# FPGA_Power.net
KiCad netlist of a schematic drawn in Altium Designer
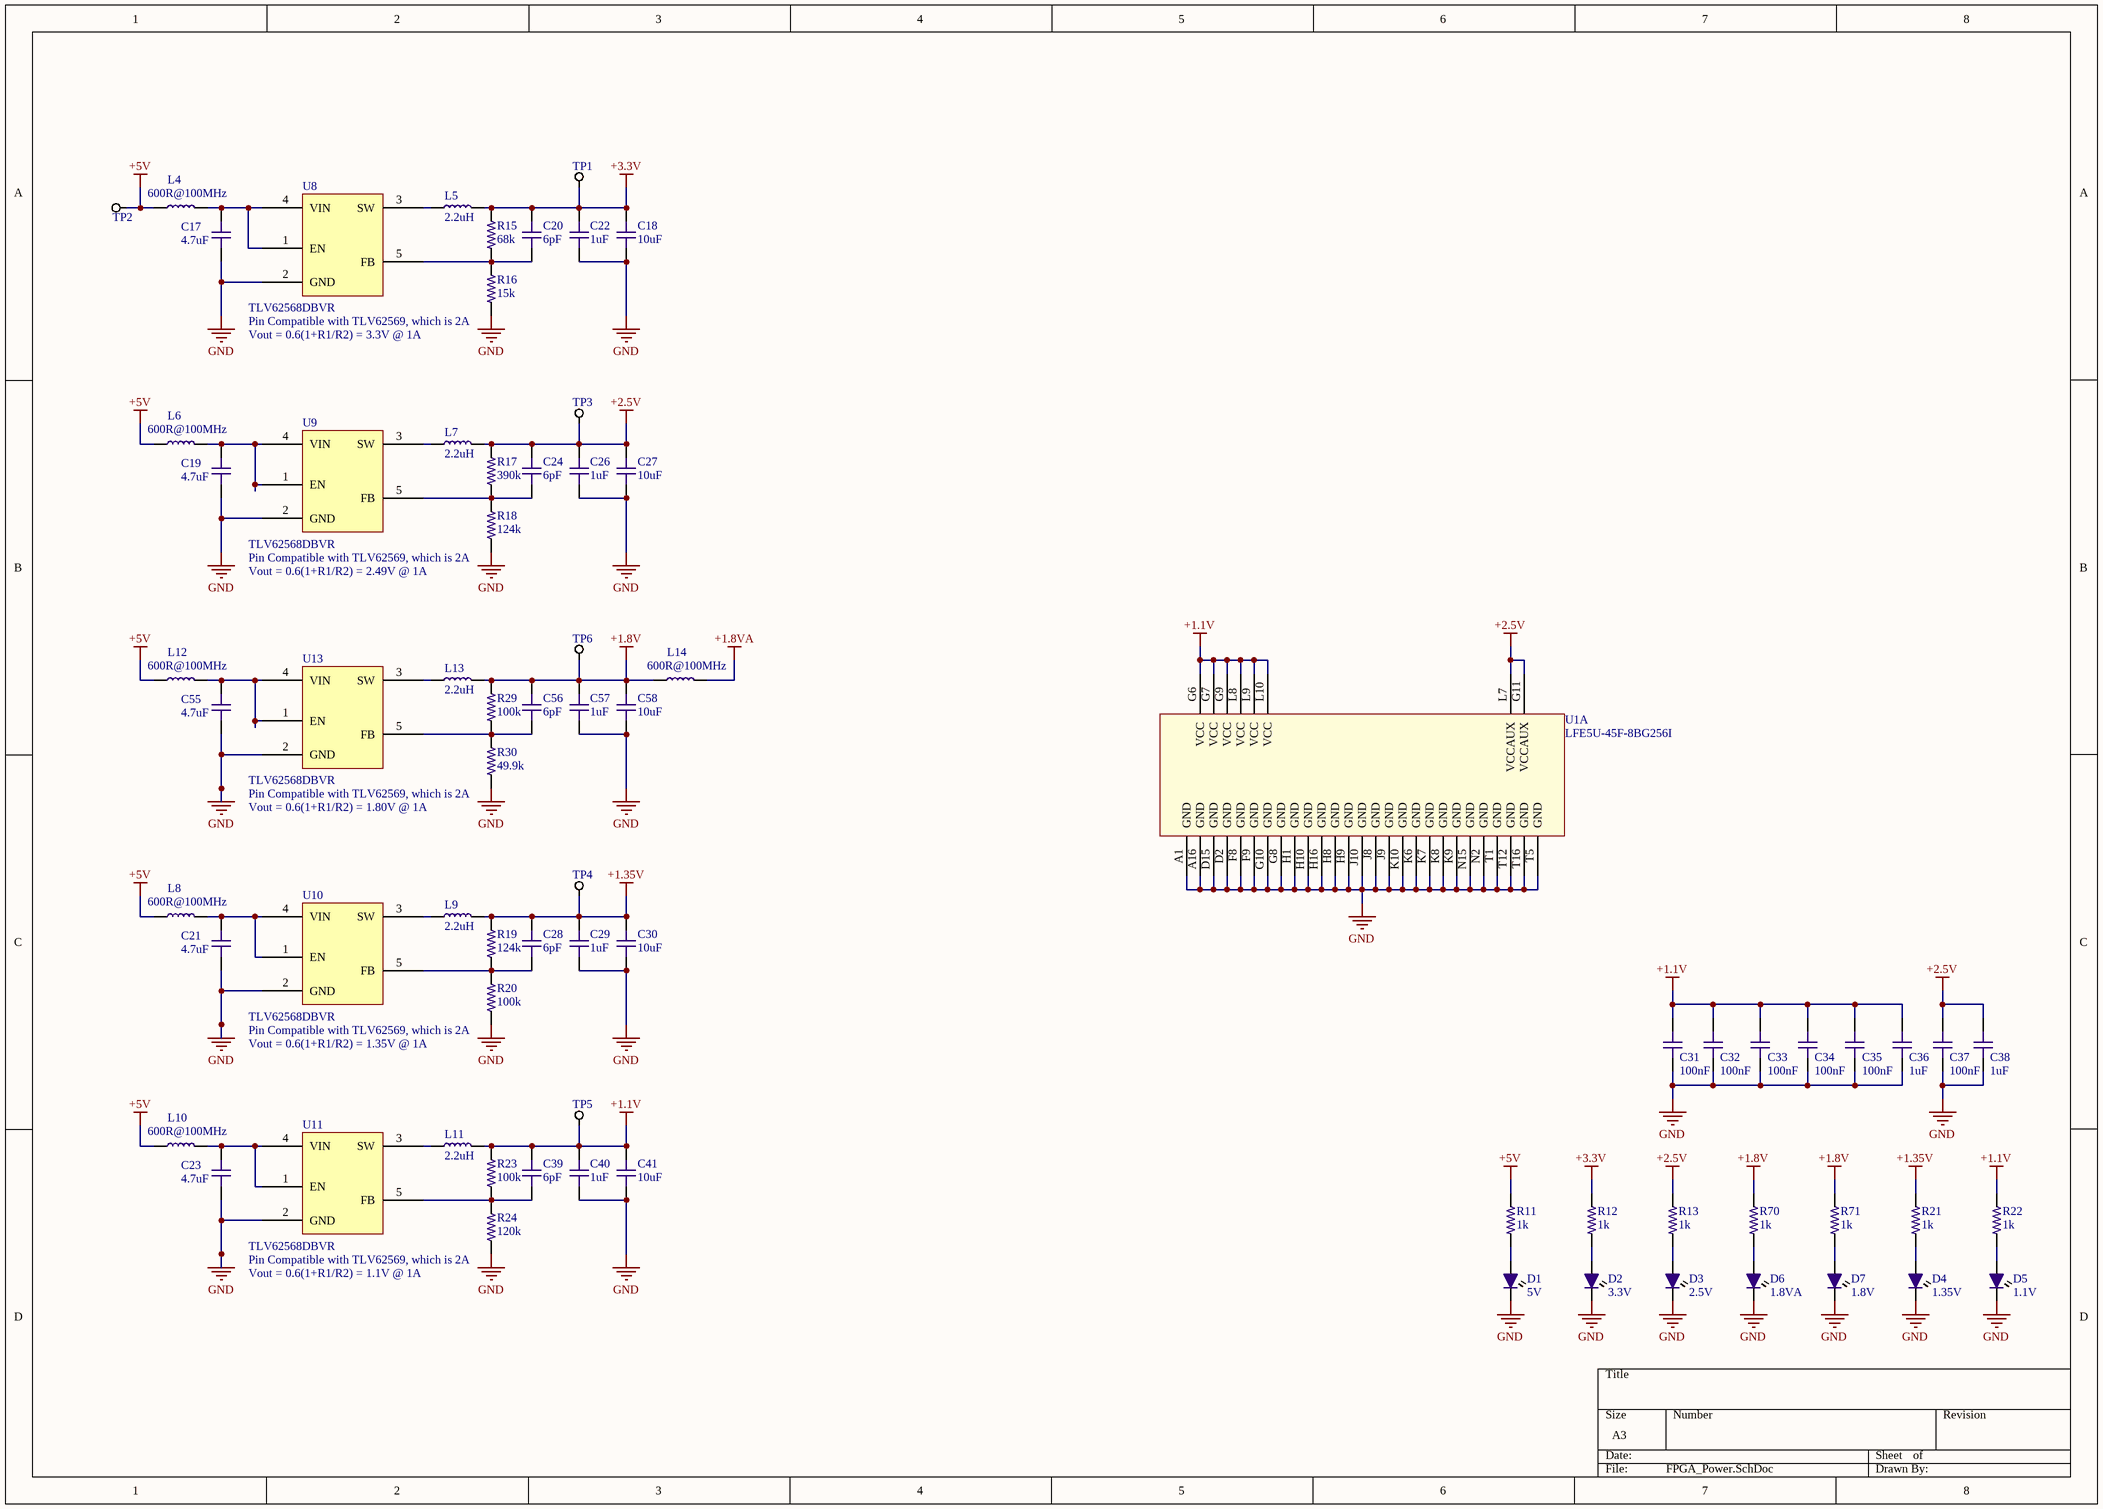
[diagram p0: FPGA_Power.SchDoc]

(export (version "E")
  (design (tool "Eeschema 10.0.6"))
  (components
    (comp (ref "C17")
      (value "4.7uF")
      (footprint "C0603-HIGH-DENSITY")
      (description "Chip Capacitor, 0603, 4.7uF, 25V, X5R")
      (fields (field (name "Comment") "4.7uF, 25V, X5R, 0603"))
      (libsource (lib "Capacitors") (part "C0603 4.7uF 25V X5R"))
    )
    (comp (ref "C18")
      (value "10uF")
      (footprint "C0603-HIGH-DENSITY")
      (description "Chip Capacitor, 0603, 10uF, 10V, X5R")
      (fields (field (name "Comment") "C0603 10uF 10V X5R"))
      (libsource (lib "Capacitors") (part "C0603 10uF 10V X5R"))
    )
    (comp (ref "C19")
      (value "4.7uF")
      (footprint "C0603-HIGH-DENSITY")
      (description "Chip Capacitor, 0603, 4.7uF, 25V, X5R")
      (fields (field (name "Comment") "4.7uF, 25V, X5R, 0603"))
      (libsource (lib "Capacitors") (part "C0603 4.7uF 25V X5R"))
    )
    (comp (ref "C20")
      (value "6pF")
      (footprint "C0603-HIGH-DENSITY")
      (description "CAP CER 6PF 50V C0G/NP0 0603")
      (fields (field (name "Comment") "CL10C060DB8NNNC"))
      (libsource (lib "Capacitors") (part "C0603 6pF 50V C0G"))
    )
    (comp (ref "C21")
      (value "4.7uF")
      (footprint "C0603-HIGH-DENSITY")
      (description "Chip Capacitor, 0603, 4.7uF, 25V, X5R")
      (fields (field (name "Comment") "4.7uF, 25V, X5R, 0603"))
      (libsource (lib "Capacitors") (part "C0603 4.7uF 25V X5R"))
    )
    (comp (ref "C22")
      (value "1uF")
      (footprint "C0603-HIGH-DENSITY")
      (description "CAP CER 1UF 25V X7R 0603")
      (fields (field (name "Comment") "C0603 1uF 25V X7R"))
      (libsource (lib "Capacitors") (part "C0603 1uF 25V X7R"))
    )
    (comp (ref "C23")
      (value "4.7uF")
      (footprint "C0603-HIGH-DENSITY")
      (description "Chip Capacitor, 0603, 4.7uF, 25V, X5R")
      (fields (field (name "Comment") "4.7uF, 25V, X5R, 0603"))
      (libsource (lib "Capacitors") (part "C0603 4.7uF 25V X5R"))
    )
    (comp (ref "C24")
      (value "6pF")
      (footprint "C0603-HIGH-DENSITY")
      (description "CAP CER 6PF 50V C0G/NP0 0603")
      (fields (field (name "Comment") "CL10C060DB8NNNC"))
      (libsource (lib "Capacitors") (part "C0603 6pF 50V C0G"))
    )
    (comp (ref "C26")
      (value "1uF")
      (footprint "C0603-HIGH-DENSITY")
      (description "CAP CER 1UF 25V X7R 0603")
      (fields (field (name "Comment") "C0603 1uF 25V X7R"))
      (libsource (lib "Capacitors") (part "C0603 1uF 25V X7R"))
    )
    (comp (ref "C27")
      (value "10uF")
      (footprint "C0603-HIGH-DENSITY")
      (description "Chip Capacitor, 0603, 10uF, 10V, X5R")
      (fields (field (name "Comment") "C0603 10uF 10V X5R"))
      (libsource (lib "Capacitors") (part "C0603 10uF 10V X5R"))
    )
    (comp (ref "C28")
      (value "6pF")
      (footprint "C0603-HIGH-DENSITY")
      (description "CAP CER 6PF 50V C0G/NP0 0603")
      (fields (field (name "Comment") "CL10C060DB8NNNC"))
      (libsource (lib "Capacitors") (part "C0603 6pF 50V C0G"))
    )
    (comp (ref "C29")
      (value "1uF")
      (footprint "C0603-HIGH-DENSITY")
      (description "CAP CER 1UF 25V X7R 0603")
      (fields (field (name "Comment") "C0603 1uF 25V X7R"))
      (libsource (lib "Capacitors") (part "C0603 1uF 25V X7R"))
    )
    (comp (ref "C30")
      (value "10uF")
      (footprint "C0603-HIGH-DENSITY")
      (description "Chip Capacitor, 0603, 10uF, 10V, X5R")
      (fields (field (name "Comment") "C0603 10uF 10V X5R"))
      (libsource (lib "Capacitors") (part "C0603 10uF 10V X5R"))
    )
    (comp (ref "C31")
      (value "100nF")
      (footprint "C0603-HIGH-DENSITY")
      (description "Chip Capacitor, 0603, 100nF, 25V, X7R")
      (fields (field (name "Comment") "C0603 100nF 25V X7R"))
      (libsource (lib "Capacitors") (part "C0603 100nF 25V X7R"))
    )
    (comp (ref "C32")
      (value "100nF")
      (footprint "C0603-HIGH-DENSITY")
      (description "Chip Capacitor, 0603, 100nF, 25V, X7R")
      (fields (field (name "Comment") "C0603 100nF 25V X7R"))
      (libsource (lib "Capacitors") (part "C0603 100nF 25V X7R"))
    )
    (comp (ref "C33")
      (value "100nF")
      (footprint "C0603-HIGH-DENSITY")
      (description "Chip Capacitor, 0603, 100nF, 25V, X7R")
      (fields (field (name "Comment") "C0603 100nF 25V X7R"))
      (libsource (lib "Capacitors") (part "C0603 100nF 25V X7R"))
    )
    (comp (ref "C34")
      (value "100nF")
      (footprint "C0603-HIGH-DENSITY")
      (description "Chip Capacitor, 0603, 100nF, 25V, X7R")
      (fields (field (name "Comment") "C0603 100nF 25V X7R"))
      (libsource (lib "Capacitors") (part "C0603 100nF 25V X7R"))
    )
    (comp (ref "C35")
      (value "100nF")
      (footprint "C0603-HIGH-DENSITY")
      (description "Chip Capacitor, 0603, 100nF, 25V, X7R")
      (fields (field (name "Comment") "C0603 100nF 25V X7R"))
      (libsource (lib "Capacitors") (part "C0603 100nF 25V X7R"))
    )
    (comp (ref "C36")
      (value "1uF")
      (footprint "C0603-HIGH-DENSITY")
      (description "CAP CER 1UF 25V X7R 0603")
      (fields (field (name "Comment") "C0603 1uF 25V X7R"))
      (libsource (lib "Capacitors") (part "C0603 1uF 25V X7R"))
    )
    (comp (ref "C37")
      (value "100nF")
      (footprint "C0603-HIGH-DENSITY")
      (description "Chip Capacitor, 0603, 100nF, 25V, X7R")
      (fields (field (name "Comment") "C0603 100nF 25V X7R"))
      (libsource (lib "Capacitors") (part "C0603 100nF 25V X7R"))
    )
    (comp (ref "C38")
      (value "1uF")
      (footprint "C0603-HIGH-DENSITY")
      (description "CAP CER 1UF 25V X7R 0603")
      (fields (field (name "Comment") "C0603 1uF 25V X7R"))
      (libsource (lib "Capacitors") (part "C0603 1uF 25V X7R"))
    )
    (comp (ref "C39")
      (value "6pF")
      (footprint "C0603-HIGH-DENSITY")
      (description "CAP CER 6PF 50V C0G/NP0 0603")
      (fields (field (name "Comment") "CL10C060DB8NNNC"))
      (libsource (lib "Capacitors") (part "C0603 6pF 50V C0G"))
    )
    (comp (ref "C40")
      (value "1uF")
      (footprint "C0603-HIGH-DENSITY")
      (description "CAP CER 1UF 25V X7R 0603")
      (fields (field (name "Comment") "C0603 1uF 25V X7R"))
      (libsource (lib "Capacitors") (part "C0603 1uF 25V X7R"))
    )
    (comp (ref "C41")
      (value "10uF")
      (footprint "C0603-HIGH-DENSITY")
      (description "Chip Capacitor, 0603, 10uF, 10V, X5R")
      (fields (field (name "Comment") "C0603 10uF 10V X5R"))
      (libsource (lib "Capacitors") (part "C0603 10uF 10V X5R"))
    )
    (comp (ref "C55")
      (value "4.7uF")
      (footprint "C0603-HIGH-DENSITY")
      (description "Chip Capacitor, 0603, 4.7uF, 25V, X5R")
      (fields (field (name "Comment") "4.7uF, 25V, X5R, 0603"))
      (libsource (lib "Capacitors") (part "C0603 4.7uF 25V X5R"))
    )
    (comp (ref "C56")
      (value "6pF")
      (footprint "C0603-HIGH-DENSITY")
      (description "CAP CER 6PF 50V C0G/NP0 0603")
      (fields (field (name "Comment") "CL10C060DB8NNNC"))
      (libsource (lib "Capacitors") (part "C0603 6pF 50V C0G"))
    )
    (comp (ref "C57")
      (value "1uF")
      (footprint "C0603-HIGH-DENSITY")
      (description "CAP CER 1UF 25V X7R 0603")
      (fields (field (name "Comment") "C0603 1uF 25V X7R"))
      (libsource (lib "Capacitors") (part "C0603 1uF 25V X7R"))
    )
    (comp (ref "C58")
      (value "10uF")
      (footprint "C0603-HIGH-DENSITY")
      (description "Chip Capacitor, 0603, 10uF, 10V, X5R")
      (fields (field (name "Comment") "C0603 10uF 10V X5R"))
      (libsource (lib "Capacitors") (part "C0603 10uF 10V X5R"))
    )
    (comp (ref "D1")
      (value "5V")
      (footprint "LED0603-IPC")
      (description "LED GREEN CLEAR 0603 SMD")
      (libsource (lib "Diodes") (part "LED 0603 Green"))
    )
    (comp (ref "D2")
      (value "3.3V")
      (footprint "LED0603-IPC")
      (description "LED GREEN CLEAR 0603 SMD")
      (libsource (lib "Diodes") (part "LED 0603 Green"))
    )
    (comp (ref "D3")
      (value "2.5V")
      (footprint "LED0603-IPC")
      (description "LED GREEN CLEAR 0603 SMD")
      (libsource (lib "Diodes") (part "LED 0603 Green"))
    )
    (comp (ref "D4")
      (value "1.35V")
      (footprint "LED0603-IPC")
      (description "LED GREEN CLEAR 0603 SMD")
      (libsource (lib "Diodes") (part "LED 0603 Green"))
    )
    (comp (ref "D5")
      (value "1.1V")
      (footprint "LED0603-IPC")
      (description "LED GREEN CLEAR 0603 SMD")
      (libsource (lib "Diodes") (part "LED 0603 Green"))
    )
    (comp (ref "D6")
      (value "1.8VA")
      (footprint "LED0603-IPC")
      (description "LED GREEN CLEAR 0603 SMD")
      (libsource (lib "Diodes") (part "LED 0603 Green"))
    )
    (comp (ref "D7")
      (value "1.8V")
      (footprint "LED0603-IPC")
      (description "LED GREEN CLEAR 0603 SMD")
      (libsource (lib "Diodes") (part "LED 0603 Green"))
    )
    (comp (ref "L4")
      (value "600R@100MHz")
      (footprint "L0603")
      (description "600 Ohms @ 100MHz 1 Ferrite Bead 0603 (1608 Metric) 500mA 380mOhm")
      (fields (field (name "Comment") "Ferrite Bead"))
      (libsource (lib "Inductors") (part "FB 0603 600R @ 100MHz"))
    )
    (comp (ref "L5")
      (value "2.2uH")
      (footprint "L1008")
      (description "2.2µH Shielded Inductor 2.05A 117mOhm Max 1008 (2520 Metric)")
      (fields (field (name "Comment") "SDEM25201B-2R2MS"))
      (libsource (lib "Inductors") (part "SDEM25201B-2R2MS"))
    )
    (comp (ref "L6")
      (value "600R@100MHz")
      (footprint "L0603")
      (description "600 Ohms @ 100MHz 1 Ferrite Bead 0603 (1608 Metric) 500mA 380mOhm")
      (fields (field (name "Comment") "Ferrite Bead"))
      (libsource (lib "Inductors") (part "FB 0603 600R @ 100MHz"))
    )
    (comp (ref "L7")
      (value "2.2uH")
      (footprint "L1008")
      (description "2.2µH Shielded Inductor 2.05A 117mOhm Max 1008 (2520 Metric)")
      (fields (field (name "Comment") "SDEM25201B-2R2MS"))
      (libsource (lib "Inductors") (part "SDEM25201B-2R2MS"))
    )
    (comp (ref "L8")
      (value "600R@100MHz")
      (footprint "L0603")
      (description "600 Ohms @ 100MHz 1 Ferrite Bead 0603 (1608 Metric) 500mA 380mOhm")
      (fields (field (name "Comment") "Ferrite Bead"))
      (libsource (lib "Inductors") (part "FB 0603 600R @ 100MHz"))
    )
    (comp (ref "L9")
      (value "2.2uH")
      (footprint "L1008")
      (description "2.2µH Shielded Inductor 2.05A 117mOhm Max 1008 (2520 Metric)")
      (fields (field (name "Comment") "SDEM25201B-2R2MS"))
      (libsource (lib "Inductors") (part "SDEM25201B-2R2MS"))
    )
    (comp (ref "L10")
      (value "600R@100MHz")
      (footprint "L0603")
      (description "600 Ohms @ 100MHz 1 Ferrite Bead 0603 (1608 Metric) 500mA 380mOhm")
      (fields (field (name "Comment") "Ferrite Bead"))
      (libsource (lib "Inductors") (part "FB 0603 600R @ 100MHz"))
    )
    (comp (ref "L11")
      (value "2.2uH")
      (footprint "L1008")
      (description "2.2µH Shielded Inductor 2.05A 117mOhm Max 1008 (2520 Metric)")
      (fields (field (name "Comment") "SDEM25201B-2R2MS"))
      (libsource (lib "Inductors") (part "SDEM25201B-2R2MS"))
    )
    (comp (ref "L12")
      (value "600R@100MHz")
      (footprint "L0603")
      (description "600 Ohms @ 100MHz 1 Ferrite Bead 0603 (1608 Metric) 500mA 380mOhm")
      (fields (field (name "Comment") "Ferrite Bead"))
      (libsource (lib "Inductors") (part "FB 0603 600R @ 100MHz"))
    )
    (comp (ref "L13")
      (value "2.2uH")
      (footprint "L1008")
      (description "2.2µH Shielded Inductor 2.05A 117mOhm Max 1008 (2520 Metric)")
      (fields (field (name "Comment") "SDEM25201B-2R2MS"))
      (libsource (lib "Inductors") (part "SDEM25201B-2R2MS"))
    )
    (comp (ref "L14")
      (value "600R@100MHz")
      (footprint "L0603")
      (description "600 Ohms @ 100MHz 1 Ferrite Bead 0603 (1608 Metric) 500mA 380mOhm")
      (fields (field (name "Comment") "Ferrite Bead"))
      (libsource (lib "Inductors") (part "FB 0603 600R @ 100MHz"))
    )
    (comp (ref "R11")
      (value "1k")
      (footprint "R0603-IPC-1K")
      (description "RES SMD 1K OHM 1% 1/10W 0603")
      (fields (field (name "TOLERANCE") "±1%") (field (name "Comment") "R0603 1K 1%"))
      (libsource (lib "Resistors") (part "R0603 1K 1%"))
    )
    (comp (ref "R12")
      (value "1k")
      (footprint "R0603-IPC-1K")
      (description "RES SMD 1K OHM 1% 1/10W 0603")
      (fields (field (name "TOLERANCE") "±1%") (field (name "Comment") "R0603 1K 1%"))
      (libsource (lib "Resistors") (part "R0603 1K 1%"))
    )
    (comp (ref "R13")
      (value "1k")
      (footprint "R0603-IPC-1K")
      (description "RES SMD 1K OHM 1% 1/10W 0603")
      (fields (field (name "TOLERANCE") "±1%") (field (name "Comment") "R0603 1K 1%"))
      (libsource (lib "Resistors") (part "R0603 1K 1%"))
    )
    (comp (ref "R15")
      (value "68k")
      (footprint "R0603-HIGH-DENSITY")
      (description "RES SMD 68K OHM 1% 1/5W 0603")
      (fields (field (name "Comment") "R0603 68K 1%"))
      (libsource (lib "Resistors") (part "R0603 68K 0.1%"))
    )
    (comp (ref "R16")
      (value "15k")
      (footprint "R0603-HIGH-DENSITY")
      (description "RES SMD 15K OHM 1% 1/10W 0603")
      (fields (field (name "Comment") "R0603 15K 1%"))
      (libsource (lib "Resistors") (part "R0603 15K 1%"))
    )
    (comp (ref "R17")
      (value "390k")
      (footprint "R0603-HIGH-DENSITY")
      (description "RES SMD 390K OHM 0.1% 1/10W 0603")
      (fields (field (name "Comment") "R0603 390k 0.1%"))
      (libsource (lib "Resistors") (part "R0603 390k 0.1%"))
    )
    (comp (ref "R18")
      (value "124k")
      (footprint "R0603-HIGH-DENSITY")
      (description "RES SMD 124K OHM 1% 1/10W 0603")
      (fields (field (name "Comment") "R0603 124K 1%"))
      (libsource (lib "Resistors") (part "R0603 124K 1%"))
    )
    (comp (ref "R19")
      (value "124k")
      (footprint "R0603-HIGH-DENSITY")
      (description "RES SMD 124K OHM 1% 1/10W 0603")
      (fields (field (name "Comment") "R0603 124K 1%"))
      (libsource (lib "Resistors") (part "R0603 124K 1%"))
    )
    (comp (ref "R20")
      (value "100k")
      (footprint "R0603-HIGH-DENSITY")
      (description "RES SMD 100K OHM 1% 1/10W 0603")
      (fields (field (name "Comment") "R0603 100K 1%"))
      (libsource (lib "Resistors") (part "R0603 100K 1%"))
    )
    (comp (ref "R21")
      (value "1k")
      (footprint "R0603-IPC-1K")
      (description "RES SMD 1K OHM 1% 1/10W 0603")
      (fields (field (name "TOLERANCE") "±1%") (field (name "Comment") "R0603 1K 1%"))
      (libsource (lib "Resistors") (part "R0603 1K 1%"))
    )
    (comp (ref "R22")
      (value "1k")
      (footprint "R0603-IPC-1K")
      (description "RES SMD 1K OHM 1% 1/10W 0603")
      (fields (field (name "TOLERANCE") "±1%") (field (name "Comment") "R0603 1K 1%"))
      (libsource (lib "Resistors") (part "R0603 1K 1%"))
    )
    (comp (ref "R23")
      (value "100k")
      (footprint "R0603-HIGH-DENSITY")
      (description "RES SMD 100K OHM 1% 1/10W 0603")
      (fields (field (name "Comment") "R0603 100K 1%"))
      (libsource (lib "Resistors") (part "R0603 100K 1%"))
    )
    (comp (ref "R24")
      (value "120k")
      (footprint "R0603-HIGH-DENSITY")
      (description "RES SMD 120K OHM 1% 1/10W 0603")
      (fields (field (name "TOLERANCE") "±1%") (field (name "POWER") "0.1W"))
      (libsource (lib "Resistors") (part "R0603 120k 1%"))
    )
    (comp (ref "R29")
      (value "100k")
      (footprint "R0603-HIGH-DENSITY")
      (description "RES SMD 100K OHM 1% 1/10W 0603")
      (fields (field (name "Comment") "R0603 100K 1%"))
      (libsource (lib "Resistors") (part "R0603 100K 1%"))
    )
    (comp (ref "R30")
      (value "49.9k")
      (footprint "R0603-HIGH-DENSITY")
      (description "RES SMD 49.9K OHM 1% 1/10W 0603")
      (fields (field (name "TOLERANCE") "±1%") (field (name "Comment") "R0603 49.9K 1%"))
      (libsource (lib "Resistors") (part "R0603 49.9K 1%"))
    )
    (comp (ref "R70")
      (value "1k")
      (footprint "R0603-IPC-1K")
      (description "RES SMD 1K OHM 1% 1/10W 0603")
      (fields (field (name "TOLERANCE") "±1%") (field (name "Comment") "R0603 1K 1%"))
      (libsource (lib "Resistors") (part "R0603 1K 1%"))
    )
    (comp (ref "R71")
      (value "1k")
      (footprint "R0603-IPC-1K")
      (description "RES SMD 1K OHM 1% 1/10W 0603")
      (fields (field (name "TOLERANCE") "±1%") (field (name "Comment") "R0603 1K 1%"))
      (libsource (lib "Resistors") (part "R0603 1K 1%"))
    )
    (comp (ref "TP1")
      (value "3V3")
      (footprint "Testpoint_TH")
      (description "Through-hole testpoint hook")
      (libsource (lib "Virtual Parts") (part "Testpoint_TH"))
    )
    (comp (ref "TP2")
      (value "5V0")
      (footprint "Testpoint_TH")
      (description "Through-hole testpoint hook")
      (libsource (lib "Virtual Parts") (part "Testpoint_TH"))
    )
    (comp (ref "TP3")
      (value "2V5")
      (footprint "Testpoint_TH")
      (description "Through-hole testpoint hook")
      (libsource (lib "Virtual Parts") (part "Testpoint_TH"))
    )
    (comp (ref "TP4")
      (value "1V35")
      (footprint "Testpoint_TH")
      (description "Through-hole testpoint hook")
      (libsource (lib "Virtual Parts") (part "Testpoint_TH"))
    )
    (comp (ref "TP5")
      (value "1V1")
      (footprint "Testpoint_TH")
      (description "Through-hole testpoint hook")
      (libsource (lib "Virtual Parts") (part "Testpoint_TH"))
    )
    (comp (ref "TP6")
      (value "1V8")
      (footprint "Testpoint_TH")
      (description "Through-hole testpoint hook")
      (libsource (lib "Virtual Parts") (part "Testpoint_TH"))
    )
    (comp (ref "U1")
      (value "LFE5U-45F-8BG256I")
      (footprint "caBGA256")
      (description "Lattice ECP5 45k LUTs \r\nIC FPGA 197 I/O 256CABGA")
      (libsource (lib "Integrated Circuits") (part "ECP5-45F-CABGA256"))
    )
    (comp (ref "U8")
      (value "TLV62568DBVR")
      (footprint "DBV0005A")
      (description "IC REG BUCK ADJ 1A SOT23-5")
      (libsource (lib "Integrated Circuits") (part "TLV62568"))
    )
    (comp (ref "U9")
      (value "TLV62568DBVR")
      (footprint "DBV0005A")
      (description "IC REG BUCK ADJ 1A SOT23-5")
      (libsource (lib "Integrated Circuits") (part "TLV62568"))
    )
    (comp (ref "U10")
      (value "TLV62568DBVR")
      (footprint "DBV0005A")
      (description "IC REG BUCK ADJ 1A SOT23-5")
      (libsource (lib "Integrated Circuits") (part "TLV62568"))
    )
    (comp (ref "U11")
      (value "TLV62568DBVR")
      (footprint "DBV0005A")
      (description "IC REG BUCK ADJ 1A SOT23-5")
      (libsource (lib "Integrated Circuits") (part "TLV62568"))
    )
    (comp (ref "U13")
      (value "TLV62568DBVR")
      (footprint "DBV0005A")
      (description "IC REG BUCK ADJ 1A SOT23-5")
      (libsource (lib "Integrated Circuits") (part "TLV62568"))
    )
  )
  (nets
    (net (code "1") (name "+1.1V") (class "Default")
      (node (ref "C31") (pin "2") (pintype "passive"))
      (node (ref "C32") (pin "2") (pintype "passive"))
      (node (ref "C33") (pin "2") (pintype "passive"))
      (node (ref "C34") (pin "2") (pintype "passive"))
      (node (ref "C35") (pin "2") (pintype "passive"))
      (node (ref "C36") (pin "2") (pintype "passive"))
      (node (ref "C39") (pin "2") (pintype "passive"))
      (node (ref "C40") (pin "2") (pintype "passive"))
      (node (ref "C41") (pin "2") (pintype "passive"))
      (node (ref "L11") (pin "2") (pintype "passive"))
      (node (ref "R22") (pin "2") (pintype "passive"))
      (node (ref "R23") (pin "2") (pintype "passive"))
      (node (ref "TP5") (pin "1") (pinfunction "1_1") (pintype "passive"))
      (node (ref "U1") (pin "G6") (pinfunction "VCC_G6") (pintype "power_in"))
      (node (ref "U1") (pin "G7") (pinfunction "VCC_G7") (pintype "power_in"))
      (node (ref "U1") (pin "G9") (pinfunction "VCC_G9") (pintype "power_in"))
      (node (ref "U1") (pin "L10") (pinfunction "VCC_L10") (pintype "power_in"))
      (node (ref "U1") (pin "L8") (pinfunction "VCC_L8") (pintype "power_in"))
      (node (ref "U1") (pin "L9") (pinfunction "VCC_L9") (pintype "power_in"))
    )
    (net (code "2") (name "+1.8V") (class "Default")
      (node (ref "C56") (pin "2") (pintype "passive"))
      (node (ref "C57") (pin "2") (pintype "passive"))
      (node (ref "C58") (pin "2") (pintype "passive"))
      (node (ref "L13") (pin "2") (pintype "passive"))
      (node (ref "L14") (pin "1") (pintype "passive"))
      (node (ref "R29") (pin "2") (pintype "passive"))
      (node (ref "R70") (pin "2") (pintype "passive"))
      (node (ref "R71") (pin "2") (pintype "passive"))
      (node (ref "TP6") (pin "1") (pinfunction "1_1") (pintype "passive"))
    )
    (net (code "3") (name "+1.8VA") (class "Default") (node (ref "L14") (pin "2") (pintype "passive")))
    (net (code "4") (name "+1.35V") (class "Default")
      (node (ref "C28") (pin "2") (pintype "passive"))
      (node (ref "C29") (pin "2") (pintype "passive"))
      (node (ref "C30") (pin "2") (pintype "passive"))
      (node (ref "L9") (pin "2") (pintype "passive"))
      (node (ref "R19") (pin "2") (pintype "passive"))
      (node (ref "R21") (pin "2") (pintype "passive"))
      (node (ref "TP4") (pin "1") (pinfunction "1_1") (pintype "passive"))
    )
    (net (code "5") (name "+2.5V") (class "Default")
      (node (ref "C24") (pin "2") (pintype "passive"))
      (node (ref "C26") (pin "2") (pintype "passive"))
      (node (ref "C27") (pin "2") (pintype "passive"))
      (node (ref "C37") (pin "2") (pintype "passive"))
      (node (ref "C38") (pin "2") (pintype "passive"))
      (node (ref "L7") (pin "2") (pintype "passive"))
      (node (ref "R13") (pin "2") (pintype "passive"))
      (node (ref "R17") (pin "2") (pintype "passive"))
      (node (ref "TP3") (pin "1") (pinfunction "1_1") (pintype "passive"))
      (node (ref "U1") (pin "G11") (pinfunction "VCCAUX_G11") (pintype "power_in"))
      (node (ref "U1") (pin "L7") (pinfunction "VCCAUX_L7") (pintype "power_in"))
    )
    (net (code "6") (name "+3.3V") (class "Default")
      (node (ref "C18") (pin "2") (pintype "passive"))
      (node (ref "C20") (pin "2") (pintype "passive"))
      (node (ref "C22") (pin "2") (pintype "passive"))
      (node (ref "L5") (pin "2") (pintype "passive"))
      (node (ref "R12") (pin "2") (pintype "passive"))
      (node (ref "R15") (pin "2") (pintype "passive"))
      (node (ref "TP1") (pin "1") (pinfunction "1_1") (pintype "passive"))
    )
    (net (code "7") (name "+5V") (class "Default")
      (node (ref "L10") (pin "1") (pintype "passive"))
      (node (ref "L12") (pin "1") (pintype "passive"))
      (node (ref "L4") (pin "1") (pintype "passive"))
      (node (ref "L6") (pin "1") (pintype "passive"))
      (node (ref "L8") (pin "1") (pintype "passive"))
      (node (ref "R11") (pin "2") (pintype "passive"))
      (node (ref "TP2") (pin "1") (pinfunction "1_1") (pintype "passive"))
    )
    (net (code "8") (name "GND") (class "Default")
      (node (ref "C17") (pin "1") (pintype "passive"))
      (node (ref "C18") (pin "1") (pintype "passive"))
      (node (ref "C19") (pin "1") (pintype "passive"))
      (node (ref "C21") (pin "1") (pintype "passive"))
      (node (ref "C22") (pin "1") (pintype "passive"))
      (node (ref "C23") (pin "1") (pintype "passive"))
      (node (ref "C26") (pin "1") (pintype "passive"))
      (node (ref "C27") (pin "1") (pintype "passive"))
      (node (ref "C29") (pin "1") (pintype "passive"))
      (node (ref "C30") (pin "1") (pintype "passive"))
      (node (ref "C31") (pin "1") (pintype "passive"))
      (node (ref "C32") (pin "1") (pintype "passive"))
      (node (ref "C33") (pin "1") (pintype "passive"))
      (node (ref "C34") (pin "1") (pintype "passive"))
      (node (ref "C35") (pin "1") (pintype "passive"))
      (node (ref "C36") (pin "1") (pintype "passive"))
      (node (ref "C37") (pin "1") (pintype "passive"))
      (node (ref "C38") (pin "1") (pintype "passive"))
      (node (ref "C40") (pin "1") (pintype "passive"))
      (node (ref "C41") (pin "1") (pintype "passive"))
      (node (ref "C55") (pin "1") (pintype "passive"))
      (node (ref "C57") (pin "1") (pintype "passive"))
      (node (ref "C58") (pin "1") (pintype "passive"))
      (node (ref "D1") (pin "K") (pintype "passive"))
      (node (ref "D2") (pin "K") (pintype "passive"))
      (node (ref "D3") (pin "K") (pintype "passive"))
      (node (ref "D4") (pin "K") (pintype "passive"))
      (node (ref "D5") (pin "K") (pintype "passive"))
      (node (ref "D6") (pin "K") (pintype "passive"))
      (node (ref "D7") (pin "K") (pintype "passive"))
      (node (ref "R16") (pin "1") (pintype "passive"))
      (node (ref "R18") (pin "1") (pintype "passive"))
      (node (ref "R20") (pin "1") (pintype "passive"))
      (node (ref "R24") (pin "1") (pintype "passive"))
      (node (ref "R30") (pin "1") (pintype "passive"))
      (node (ref "U1") (pin "A1") (pinfunction "GND_A1") (pintype "power_in"))
      (node (ref "U1") (pin "A16") (pinfunction "GND_A16") (pintype "power_in"))
      (node (ref "U1") (pin "D15") (pinfunction "GND_D15") (pintype "power_in"))
      (node (ref "U1") (pin "D2") (pinfunction "GND_D2") (pintype "power_in"))
      (node (ref "U1") (pin "F8") (pinfunction "GND_F8") (pintype "power_in"))
      (node (ref "U1") (pin "F9") (pinfunction "GND_F9") (pintype "power_in"))
      (node (ref "U1") (pin "G10") (pinfunction "GND_G10") (pintype "power_in"))
      (node (ref "U1") (pin "G8") (pinfunction "GND_G8") (pintype "power_in"))
      (node (ref "U1") (pin "H1") (pinfunction "GND_H1") (pintype "power_in"))
      (node (ref "U1") (pin "H10") (pinfunction "GND_H10") (pintype "power_in"))
      (node (ref "U1") (pin "H16") (pinfunction "GND_H16") (pintype "power_in"))
      (node (ref "U1") (pin "H8") (pinfunction "GND_H8") (pintype "power_in"))
      (node (ref "U1") (pin "H9") (pinfunction "GND_H9") (pintype "power_in"))
      (node (ref "U1") (pin "J10") (pinfunction "GND_J10") (pintype "power_in"))
      (node (ref "U1") (pin "J8") (pinfunction "GND_J8") (pintype "power_in"))
      (node (ref "U1") (pin "J9") (pinfunction "GND_J9") (pintype "power_in"))
      (node (ref "U1") (pin "K10") (pinfunction "GND_K10") (pintype "power_in"))
      (node (ref "U1") (pin "K6") (pinfunction "GND_K6") (pintype "power_in"))
      (node (ref "U1") (pin "K7") (pinfunction "GND_K7") (pintype "power_in"))
      (node (ref "U1") (pin "K8") (pinfunction "GND_K8") (pintype "power_in"))
      (node (ref "U1") (pin "K9") (pinfunction "GND_K9") (pintype "power_in"))
      (node (ref "U1") (pin "N15") (pinfunction "GND_N15") (pintype "power_in"))
      (node (ref "U1") (pin "N2") (pinfunction "GND_N2") (pintype "power_in"))
      (node (ref "U1") (pin "T1") (pinfunction "GND_T1") (pintype "power_in"))
      (node (ref "U1") (pin "T12") (pinfunction "GND_T12") (pintype "power_in"))
      (node (ref "U1") (pin "T16") (pinfunction "GND_T16") (pintype "power_in"))
      (node (ref "U1") (pin "T5") (pinfunction "GND_T5") (pintype "power_in"))
      (node (ref "U10") (pin "2") (pinfunction "GND_2") (pintype "passive"))
      (node (ref "U11") (pin "2") (pinfunction "GND_2") (pintype "passive"))
      (node (ref "U13") (pin "2") (pinfunction "GND_2") (pintype "passive"))
      (node (ref "U8") (pin "2") (pinfunction "GND_2") (pintype "passive"))
      (node (ref "U9") (pin "2") (pinfunction "GND_2") (pintype "passive"))
    )
    (net (code "9") (name "Net-(D1-PadA)") (class "Default")
      (node (ref "D1") (pin "A") (pintype "passive"))
      (node (ref "R11") (pin "1") (pintype "passive"))
    )
    (net (code "10") (name "Net-(D2-PadA)") (class "Default")
      (node (ref "D2") (pin "A") (pintype "passive"))
      (node (ref "R12") (pin "1") (pintype "passive"))
    )
    (net (code "11") (name "Net-(D3-PadA)") (class "Default")
      (node (ref "D3") (pin "A") (pintype "passive"))
      (node (ref "R13") (pin "1") (pintype "passive"))
    )
    (net (code "12") (name "Net-(D4-PadA)") (class "Default")
      (node (ref "D4") (pin "A") (pintype "passive"))
      (node (ref "R21") (pin "1") (pintype "passive"))
    )
    (net (code "13") (name "Net-(D5-PadA)") (class "Default")
      (node (ref "D5") (pin "A") (pintype "passive"))
      (node (ref "R22") (pin "1") (pintype "passive"))
    )
    (net (code "14") (name "Net-(D6-PadA)") (class "Default")
      (node (ref "D6") (pin "A") (pintype "passive"))
      (node (ref "R70") (pin "1") (pintype "passive"))
    )
    (net (code "15") (name "Net-(D7-PadA)") (class "Default")
      (node (ref "D7") (pin "A") (pintype "passive"))
      (node (ref "R71") (pin "1") (pintype "passive"))
    )
    (net (code "16") (name "Net-(U8-EN)") (class "Default")
      (node (ref "C17") (pin "2") (pintype "passive"))
      (node (ref "L4") (pin "2") (pintype "passive"))
      (node (ref "U8") (pin "1") (pinfunction "EN_1") (pintype "passive"))
      (node (ref "U8") (pin "4") (pinfunction "VIN_4") (pintype "passive"))
    )
    (net (code "17") (name "Net-(U8-FB)") (class "Default")
      (node (ref "C20") (pin "1") (pintype "passive"))
      (node (ref "R15") (pin "1") (pintype "passive"))
      (node (ref "R16") (pin "2") (pintype "passive"))
      (node (ref "U8") (pin "5") (pinfunction "FB_5") (pintype "passive"))
    )
    (net (code "18") (name "Net-(U8-SW)") (class "Default")
      (node (ref "L5") (pin "1") (pintype "passive"))
      (node (ref "U8") (pin "3") (pinfunction "SW_3") (pintype "passive"))
    )
    (net (code "19") (name "Net-(U9-EN)") (class "Default")
      (node (ref "C19") (pin "2") (pintype "passive"))
      (node (ref "L6") (pin "2") (pintype "passive"))
      (node (ref "U9") (pin "1") (pinfunction "EN_1") (pintype "passive"))
      (node (ref "U9") (pin "4") (pinfunction "VIN_4") (pintype "passive"))
    )
    (net (code "20") (name "Net-(U9-FB)") (class "Default")
      (node (ref "C24") (pin "1") (pintype "passive"))
      (node (ref "R17") (pin "1") (pintype "passive"))
      (node (ref "R18") (pin "2") (pintype "passive"))
      (node (ref "U9") (pin "5") (pinfunction "FB_5") (pintype "passive"))
    )
    (net (code "21") (name "Net-(U9-SW)") (class "Default")
      (node (ref "L7") (pin "1") (pintype "passive"))
      (node (ref "U9") (pin "3") (pinfunction "SW_3") (pintype "passive"))
    )
    (net (code "22") (name "Net-(U10-EN)") (class "Default")
      (node (ref "C21") (pin "2") (pintype "passive"))
      (node (ref "L8") (pin "2") (pintype "passive"))
      (node (ref "U10") (pin "1") (pinfunction "EN_1") (pintype "passive"))
      (node (ref "U10") (pin "4") (pinfunction "VIN_4") (pintype "passive"))
    )
    (net (code "23") (name "Net-(U10-FB)") (class "Default")
      (node (ref "C28") (pin "1") (pintype "passive"))
      (node (ref "R19") (pin "1") (pintype "passive"))
      (node (ref "R20") (pin "2") (pintype "passive"))
      (node (ref "U10") (pin "5") (pinfunction "FB_5") (pintype "passive"))
    )
    (net (code "24") (name "Net-(U10-SW)") (class "Default")
      (node (ref "L9") (pin "1") (pintype "passive"))
      (node (ref "U10") (pin "3") (pinfunction "SW_3") (pintype "passive"))
    )
    (net (code "25") (name "Net-(U11-EN)") (class "Default")
      (node (ref "C23") (pin "2") (pintype "passive"))
      (node (ref "L10") (pin "2") (pintype "passive"))
      (node (ref "U11") (pin "1") (pinfunction "EN_1") (pintype "passive"))
      (node (ref "U11") (pin "4") (pinfunction "VIN_4") (pintype "passive"))
    )
    (net (code "26") (name "Net-(U11-FB)") (class "Default")
      (node (ref "C39") (pin "1") (pintype "passive"))
      (node (ref "R23") (pin "1") (pintype "passive"))
      (node (ref "R24") (pin "2") (pintype "passive"))
      (node (ref "U11") (pin "5") (pinfunction "FB_5") (pintype "passive"))
    )
    (net (code "27") (name "Net-(U11-SW)") (class "Default")
      (node (ref "L11") (pin "1") (pintype "passive"))
      (node (ref "U11") (pin "3") (pinfunction "SW_3") (pintype "passive"))
    )
    (net (code "28") (name "Net-(U13-EN)") (class "Default")
      (node (ref "C55") (pin "2") (pintype "passive"))
      (node (ref "L12") (pin "2") (pintype "passive"))
      (node (ref "U13") (pin "1") (pinfunction "EN_1") (pintype "passive"))
      (node (ref "U13") (pin "4") (pinfunction "VIN_4") (pintype "passive"))
    )
    (net (code "29") (name "Net-(U13-FB)") (class "Default")
      (node (ref "C56") (pin "1") (pintype "passive"))
      (node (ref "R29") (pin "1") (pintype "passive"))
      (node (ref "R30") (pin "2") (pintype "passive"))
      (node (ref "U13") (pin "5") (pinfunction "FB_5") (pintype "passive"))
    )
    (net (code "30") (name "Net-(U13-SW)") (class "Default")
      (node (ref "L13") (pin "1") (pintype "passive"))
      (node (ref "U13") (pin "3") (pinfunction "SW_3") (pintype "passive"))
    )
  )
)
